# spot_check.net
KiCad netlist of a schematic drawn in EAGLE
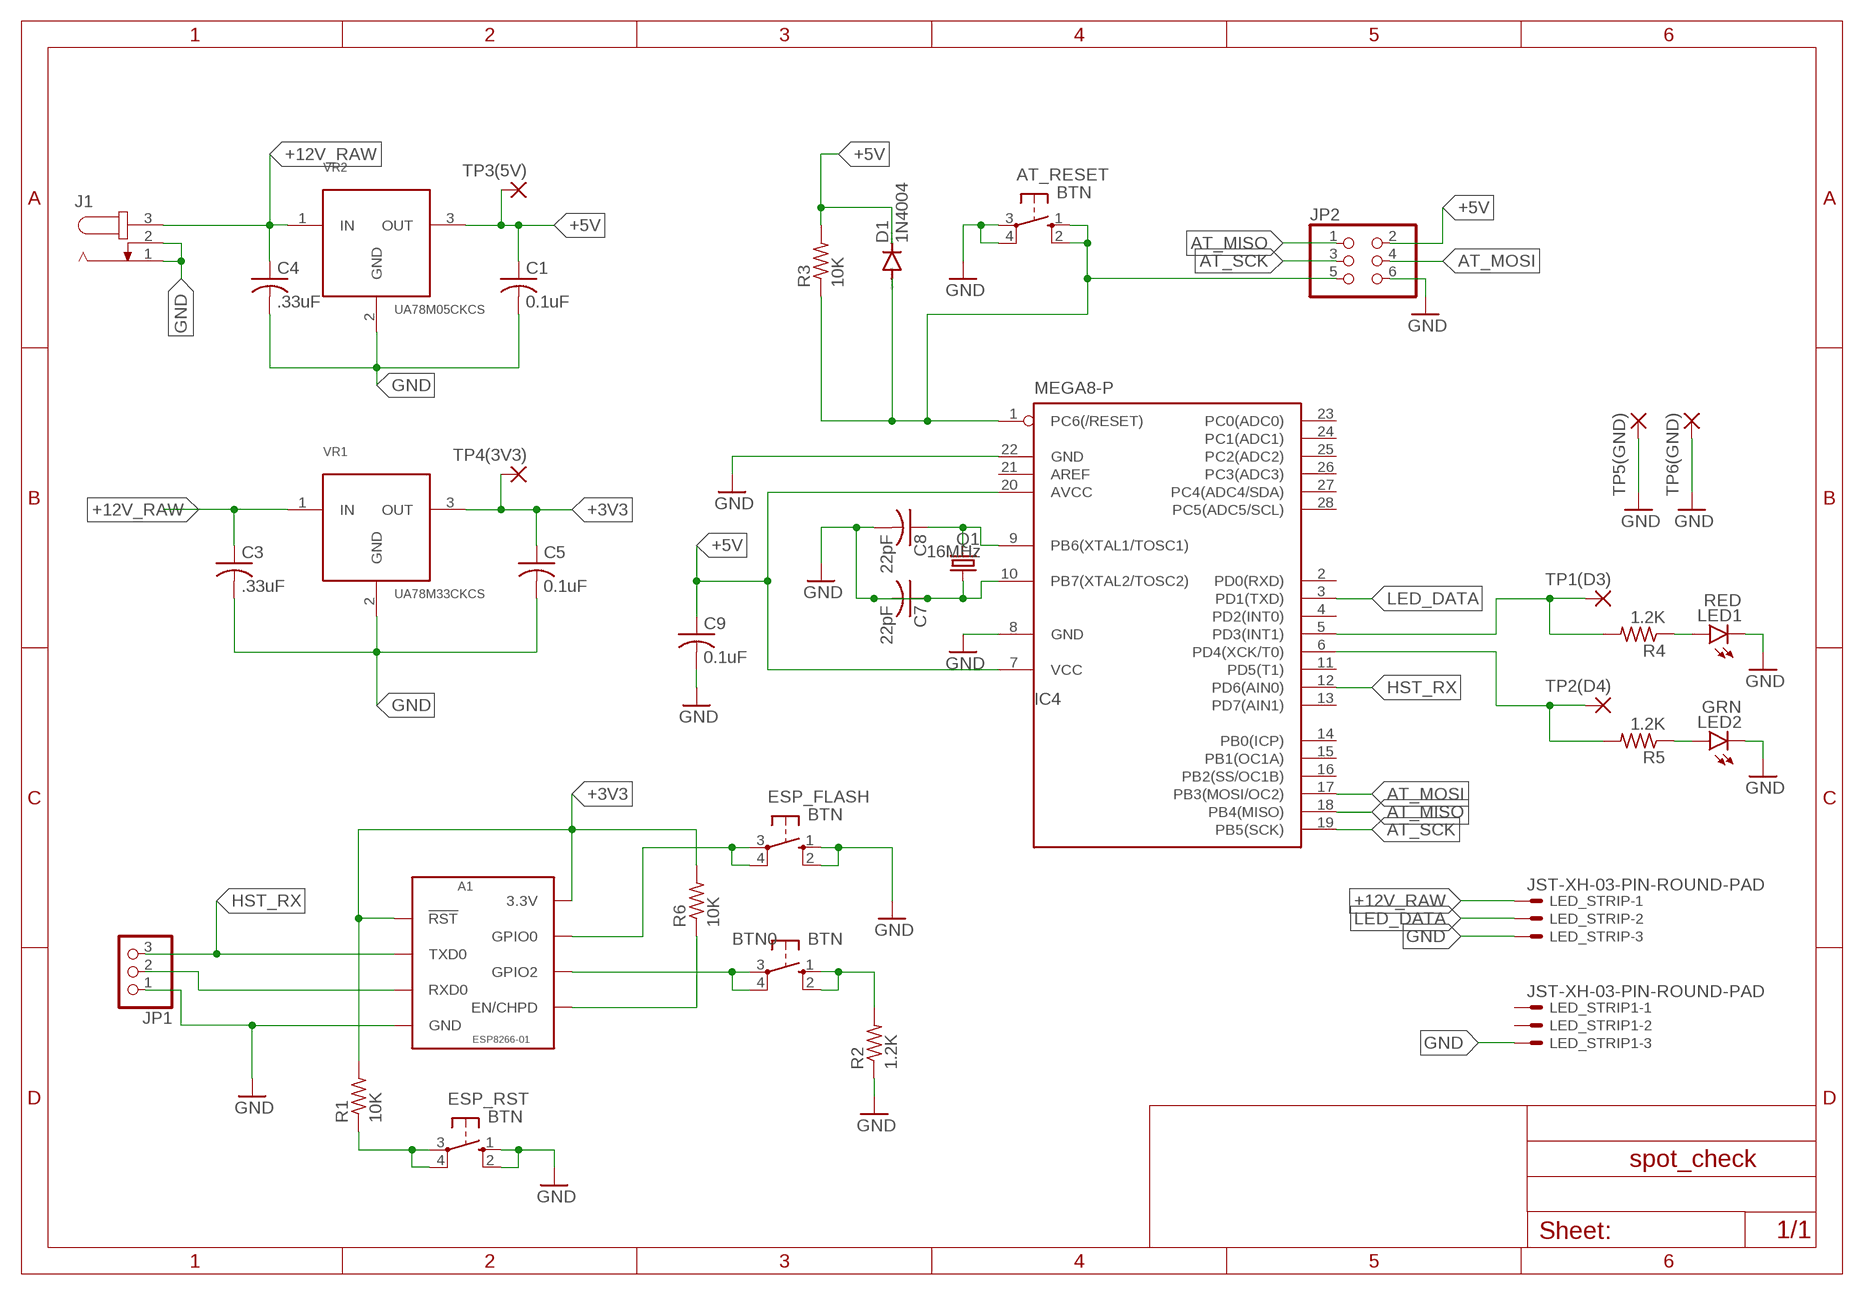
[diagram p0: schematic, sheet 1]

(export (version "E")
  (design (tool "Eeschema 10.0.6"))
  (components
    (comp (ref "A1")
      (value "ESP8266-01")
      (footprint "eagle-import:ESP8266_ESP-01_NO-SILKSCREEN")
      (fields (field (name "SPICEPREFIX") "X"))
      (libsource (lib "eagle-import") (part "ESP8266_ESP-?01"))
    )
    (comp (ref "AT_RESET")
      (value "BTN")
      (footprint "eagle-import:B3F-10XX")
      (fields (field (name "MPN") "B3F-1000") (field (name "SPICEPREFIX") "E"))
      (libsource (lib "eagle-import") (part "10-XX"))
    )
    (comp (ref "BTN0")
      (value "BTN")
      (footprint "eagle-import:B3F-10XX")
      (fields (field (name "MPN") "B3F-1000") (field (name "SPICEPREFIX") "E"))
      (libsource (lib "eagle-import") (part "10-XX"))
    )
    (comp (ref "C1")
      (value "0.1uF")
      (footprint "eagle-import:C050-024X044")
      (libsource (lib "eagle-import") (part "C-US050-024X044"))
    )
    (comp (ref "C3")
      (value ".33uF")
      (footprint "eagle-import:C050-024X044")
      (libsource (lib "eagle-import") (part "C-US050-024X044"))
    )
    (comp (ref "C4")
      (value ".33uF")
      (footprint "eagle-import:C050-024X044")
      (libsource (lib "eagle-import") (part "C-US050-024X044"))
    )
    (comp (ref "C5")
      (value "0.1uF")
      (footprint "eagle-import:C050-024X044")
      (libsource (lib "eagle-import") (part "C-US050-024X044"))
    )
    (comp (ref "C7")
      (value "22pF")
      (footprint "eagle-import:C050-024X044")
      (libsource (lib "eagle-import") (part "C-US050-024X044"))
    )
    (comp (ref "C8")
      (value "22pF")
      (footprint "eagle-import:C050-024X044")
      (libsource (lib "eagle-import") (part "C-US050-024X044"))
    )
    (comp (ref "C9")
      (value "0.1uF")
      (footprint "eagle-import:C050-024X044")
      (libsource (lib "eagle-import") (part "C-US050-024X044"))
    )
    (comp (ref "D1")
      (value "1N4004")
      (footprint "eagle-import:DO41-10")
      (fields (field (name "SPICEPREFIX") "D"))
      (libsource (lib "eagle-import") (part "1N4004"))
    )
    (comp (ref "ESP_FLASH")
      (value "BTN")
      (footprint "eagle-import:B3F-10XX")
      (fields (field (name "MPN") "B3F-1000") (field (name "SPICEPREFIX") "E"))
      (libsource (lib "eagle-import") (part "10-XX"))
    )
    (comp (ref "ESP_RST")
      (value "BTN")
      (footprint "eagle-import:B3F-10XX")
      (fields (field (name "MPN") "B3F-1000") (field (name "SPICEPREFIX") "E"))
      (libsource (lib "eagle-import") (part "10-XX"))
    )
    (comp (ref "IC4")
      (value "MEGA8-P")
      (footprint "eagle-import:DIL28-3")
      (fields (field (name "SPICEPREFIX") "X"))
      (libsource (lib "eagle-import") (part "MEGA8-P"))
    )
    (comp (ref "J1")
      (value "JACK-PLUG1")
      (footprint "eagle-import:SPC4078")
      (fields (field (name "SPICEPREFIX") "J"))
      (libsource (lib "eagle-import") (part "JACK-PLUG1"))
    )
    (comp (ref "JP1")
      (value "PINHD-1X3/90")
      (footprint "eagle-import:1X03_90")
      (fields (field (name "SPICEPREFIX") "J"))
      (libsource (lib "eagle-import") (part "PINHD-1X3/90"))
    )
    (comp (ref "JP2")
      (value "PINHD-2X3")
      (footprint "eagle-import:2X03")
      (fields (field (name "SPICEPREFIX") "X"))
      (libsource (lib "eagle-import") (part "PINHD-2X3"))
    )
    (comp (ref "LED1")
      (value "RED")
      (footprint "eagle-import:LED5MM")
      (fields (field (name "SPICEPREFIX") "L"))
      (libsource (lib "eagle-import") (part "LED5MM"))
    )
    (comp (ref "LED2")
      (value "GRN")
      (footprint "eagle-import:LED5MM")
      (fields (field (name "SPICEPREFIX") "L"))
      (libsource (lib "eagle-import") (part "LED5MM"))
    )
    (comp (ref "LED_STRIP")
      (value "JST-XH-03-PIN-ROUND-PAD")
      (footprint "eagle-import:JST-XH-03-PACKAGE-ROUND-PAD")
      (fields (field (name "SPICEPREFIX") "X"))
      (libsource (lib "eagle-import") (part "JST-XH-03-PIN-ROUND-PAD"))
    )
    (comp (ref "LED_STRIP1")
      (value "JST-XH-03-PIN-ROUND-PAD")
      (footprint "eagle-import:JST-XH-03-PACKAGE-ROUND-PAD")
      (fields (field (name "SPICEPREFIX") "X"))
      (libsource (lib "eagle-import") (part "JST-XH-03-PIN-ROUND-PAD"))
    )
    (comp (ref "Q1")
      (value "16MHz")
      (footprint "eagle-import:HC49_S")
      (fields (field (name "SPICEPREFIX") "B"))
      (libsource (lib "eagle-import") (part "CRYSTALHC49S"))
    )
    (comp (ref "R1")
      (value "10K")
      (footprint "eagle-import:0207_10")
      (libsource (lib "eagle-import") (part "R-US_0207/10"))
    )
    (comp (ref "R2")
      (value "1.2K")
      (footprint "eagle-import:0207_10")
      (libsource (lib "eagle-import") (part "R-US_0207/10"))
    )
    (comp (ref "R3")
      (value "10K")
      (footprint "eagle-import:0207_10")
      (libsource (lib "eagle-import") (part "R-US_0207/10"))
    )
    (comp (ref "R4")
      (value "1.2K")
      (footprint "eagle-import:0207_10")
      (libsource (lib "eagle-import") (part "R-US_0207/10"))
    )
    (comp (ref "R5")
      (value "1.2K")
      (footprint "eagle-import:0207_10")
      (libsource (lib "eagle-import") (part "R-US_0207/10"))
    )
    (comp (ref "R6")
      (value "10K")
      (footprint "eagle-import:0207_10")
      (libsource (lib "eagle-import") (part "R-US_0207/10"))
    )
    (comp (ref "TP1(D3)")
      (value "2,54/0,8")
      (footprint "eagle-import:2,54_0,8")
      (fields (field (name "SPICEPREFIX") "X"))
      (libsource (lib "eagle-import") (part "2,54/0,8"))
    )
    (comp (ref "TP2(D4)")
      (value "2,54/0,8")
      (footprint "eagle-import:2,54_0,8")
      (fields (field (name "SPICEPREFIX") "X"))
      (libsource (lib "eagle-import") (part "2,54/0,8"))
    )
    (comp (ref "TP3(5V)")
      (value "2,54/0,8")
      (footprint "eagle-import:2,54_0,8")
      (fields (field (name "SPICEPREFIX") "X"))
      (libsource (lib "eagle-import") (part "2,54/0,8"))
    )
    (comp (ref "TP4(3V3)")
      (value "2,54/0,8")
      (footprint "eagle-import:2,54_0,8")
      (fields (field (name "SPICEPREFIX") "X"))
      (libsource (lib "eagle-import") (part "2,54/0,8"))
    )
    (comp (ref "TP5(GND)")
      (value "2,54/0,8")
      (footprint "eagle-import:2,54_0,8")
      (fields (field (name "SPICEPREFIX") "X"))
      (libsource (lib "eagle-import") (part "2,54/0,8"))
    )
    (comp (ref "TP6(GND)")
      (value "2,54/0,8")
      (footprint "eagle-import:2,54_0,8")
      (fields (field (name "SPICEPREFIX") "X"))
      (libsource (lib "eagle-import") (part "2,54/0,8"))
    )
    (comp (ref "VR1")
      (value "UA78M33CKCS")
      (footprint "eagle-import:TO-220-3")
      (fields (field (name "SPICEPREFIX") "J"))
      (libsource (lib "eagle-import") (part "UA78M33CKCS"))
    )
    (comp (ref "VR2")
      (value "UA78M05CKCS")
      (footprint "eagle-import:TO-220-3")
      (fields (field (name "SPICEPREFIX") "J"))
      (libsource (lib "eagle-import") (part "UA78M33CKCS"))
    )
  )
  (nets
    (net (code "1") (name "+3V3") (class "Default")
      (node (ref "A1") (pin "3V3") (pinfunction "3.3V_3V3") (pintype "passive"))
      (node (ref "A1") (pin "RST") (pinfunction "~{RST}_RST") (pintype "bidirectional"))
      (node (ref "C5") (pin "1") (pinfunction "1_1") (pintype "passive"))
      (node (ref "R1") (pin "2") (pinfunction "2_2") (pintype "passive"))
      (node (ref "R6") (pin "2") (pinfunction "2_2") (pintype "passive"))
      (node (ref "TP4(3V3)") (pin "1") (pinfunction "P_1") (pintype "passive"))
      (node (ref "VR1") (pin "3") (pinfunction "OUT_3") (pintype "output"))
    )
    (net (code "2") (name "+5V") (class "Default")
      (node (ref "C1") (pin "1") (pinfunction "1_1") (pintype "passive"))
      (node (ref "C9") (pin "1") (pinfunction "1_1") (pintype "passive"))
      (node (ref "D1") (pin "C") (pinfunction "C_C") (pintype "passive"))
      (node (ref "IC4") (pin "20") (pinfunction "AVCC_20") (pintype "power_in"))
      (node (ref "IC4") (pin "7") (pinfunction "VCC_7") (pintype "power_in"))
      (node (ref "JP2") (pin "2") (pinfunction "2_2") (pintype "passive"))
      (node (ref "R3") (pin "2") (pinfunction "2_2") (pintype "passive"))
      (node (ref "TP3(5V)") (pin "1") (pinfunction "P_1") (pintype "passive"))
      (node (ref "VR2") (pin "3") (pinfunction "OUT_3") (pintype "output"))
    )
    (net (code "3") (name "+12V_RAW") (class "Default")
      (node (ref "C3") (pin "1") (pinfunction "1_1") (pintype "passive"))
      (node (ref "C4") (pin "1") (pinfunction "1_1") (pintype "passive"))
      (node (ref "J1") (pin "3") (pinfunction "3_3") (pintype "passive"))
      (node (ref "LED_STRIP") (pin "1") (pinfunction "S_1") (pintype "passive"))
      (node (ref "VR1") (pin "1") (pinfunction "IN_1") (pintype "input"))
      (node (ref "VR2") (pin "1") (pinfunction "IN_1") (pintype "input"))
    )
    (net (code "4") (name "AT_MISO") (class "Default")
      (node (ref "IC4") (pin "18") (pinfunction "PB4(MISO)_18") (pintype "bidirectional"))
      (node (ref "JP2") (pin "1") (pinfunction "1_1") (pintype "passive"))
    )
    (net (code "5") (name "AT_MOSI") (class "Default")
      (node (ref "IC4") (pin "17") (pinfunction "PB3(MOSI/OC2)_17") (pintype "bidirectional"))
      (node (ref "JP2") (pin "4") (pinfunction "4_4") (pintype "passive"))
    )
    (net (code "6") (name "AT_SCK") (class "Default")
      (node (ref "IC4") (pin "19") (pinfunction "PB5(SCK)_19") (pintype "bidirectional"))
      (node (ref "JP2") (pin "3") (pinfunction "3_3") (pintype "passive"))
    )
    (net (code "7") (name "GND") (class "Default")
      (node (ref "A1") (pin "GND") (pinfunction "GND_GND") (pintype "passive"))
      (node (ref "AT_RESET") (pin "3") (pinfunction "P_3") (pintype "passive"))
      (node (ref "AT_RESET") (pin "4") (pinfunction "P1_4") (pintype "passive"))
      (node (ref "C1") (pin "2") (pinfunction "2_2") (pintype "passive"))
      (node (ref "C3") (pin "2") (pinfunction "2_2") (pintype "passive"))
      (node (ref "C4") (pin "2") (pinfunction "2_2") (pintype "passive"))
      (node (ref "C5") (pin "2") (pinfunction "2_2") (pintype "passive"))
      (node (ref "C7") (pin "1") (pinfunction "1_1") (pintype "passive"))
      (node (ref "C7") (pin "2") (pinfunction "2_2") (pintype "passive"))
      (node (ref "C8") (pin "2") (pinfunction "2_2") (pintype "passive"))
      (node (ref "C9") (pin "2") (pinfunction "2_2") (pintype "passive"))
      (node (ref "ESP_FLASH") (pin "1") (pinfunction "S_1") (pintype "passive"))
      (node (ref "ESP_FLASH") (pin "2") (pinfunction "S1_2") (pintype "passive"))
      (node (ref "ESP_RST") (pin "1") (pinfunction "S_1") (pintype "passive"))
      (node (ref "ESP_RST") (pin "2") (pinfunction "S1_2") (pintype "passive"))
      (node (ref "IC4") (pin "10") (pinfunction "PB7(XTAL2/TOSC2)_10") (pintype "bidirectional"))
      (node (ref "IC4") (pin "22") (pinfunction "GND_22") (pintype "power_in"))
      (node (ref "IC4") (pin "8") (pinfunction "GND_8") (pintype "power_in"))
      (node (ref "J1") (pin "1") (pinfunction "1_1") (pintype "passive"))
      (node (ref "J1") (pin "2") (pinfunction "2_2") (pintype "passive"))
      (node (ref "JP1") (pin "1") (pinfunction "1_1") (pintype "passive"))
      (node (ref "JP2") (pin "6") (pinfunction "6_6") (pintype "passive"))
      (node (ref "LED1") (pin "K") (pinfunction "C_K") (pintype "passive"))
      (node (ref "LED2") (pin "K") (pinfunction "C_K") (pintype "passive"))
      (node (ref "LED_STRIP") (pin "3") (pinfunction "S_3") (pintype "passive"))
      (node (ref "LED_STRIP1") (pin "3") (pinfunction "S_3") (pintype "passive"))
      (node (ref "Q1") (pin "1") (pinfunction "1_1") (pintype "passive"))
      (node (ref "R2") (pin "1") (pinfunction "1_1") (pintype "passive"))
      (node (ref "TP5(GND)") (pin "1") (pinfunction "P_1") (pintype "passive"))
      (node (ref "TP6(GND)") (pin "1") (pinfunction "P_1") (pintype "passive"))
      (node (ref "VR1") (pin "2") (pinfunction "GND_2") (pintype "bidirectional"))
      (node (ref "VR2") (pin "2") (pinfunction "GND_2") (pintype "bidirectional"))
    )
    (net (code "8") (name "HST_RX") (class "Default")
      (node (ref "A1") (pin "TX") (pinfunction "TXD0_TX") (pintype "bidirectional"))
      (node (ref "IC4") (pin "12") (pinfunction "PD6(AIN0)_12") (pintype "bidirectional"))
      (node (ref "JP1") (pin "3") (pinfunction "3_3") (pintype "passive"))
    )
    (net (code "9") (name "LED_DATA") (class "Default")
      (node (ref "IC4") (pin "3") (pinfunction "PD1(TXD)_3") (pintype "bidirectional"))
      (node (ref "LED_STRIP") (pin "2") (pinfunction "S_2") (pintype "passive"))
    )
    (net (code "10") (name "Net-(A1-EN{slash}CHPD)") (class "Default")
      (node (ref "A1") (pin "EN/CH_PD") (pinfunction "EN/CHPD_EN/CH_PD") (pintype "bidirectional"))
      (node (ref "R6") (pin "1") (pinfunction "1_1") (pintype "passive"))
    )
    (net (code "11") (name "Net-(A1-RXD0)") (class "Default")
      (node (ref "A1") (pin "RX") (pinfunction "RXD0_RX") (pintype "bidirectional"))
      (node (ref "JP1") (pin "2") (pinfunction "2_2") (pintype "passive"))
    )
    (net (code "12") (name "Net-(AT_RESET-S)") (class "Default")
      (node (ref "AT_RESET") (pin "1") (pinfunction "S_1") (pintype "passive"))
      (node (ref "AT_RESET") (pin "2") (pinfunction "S1_2") (pintype "passive"))
      (node (ref "D1") (pin "A") (pinfunction "A_A") (pintype "passive"))
      (node (ref "IC4") (pin "1") (pinfunction "PC6(/RESET)_1") (pintype "bidirectional"))
      (node (ref "JP2") (pin "5") (pinfunction "5_5") (pintype "passive"))
      (node (ref "R3") (pin "1") (pinfunction "1_1") (pintype "passive"))
    )
    (net (code "13") (name "Net-(BTN0-P)") (class "Default")
      (node (ref "A1") (pin "GPIO2") (pinfunction "GPIO2_GPIO2") (pintype "bidirectional"))
      (node (ref "BTN0") (pin "3") (pinfunction "P_3") (pintype "passive"))
      (node (ref "BTN0") (pin "4") (pinfunction "P1_4") (pintype "passive"))
    )
    (net (code "14") (name "Net-(BTN0-S)") (class "Default")
      (node (ref "BTN0") (pin "1") (pinfunction "S_1") (pintype "passive"))
      (node (ref "BTN0") (pin "2") (pinfunction "S1_2") (pintype "passive"))
      (node (ref "R2") (pin "2") (pinfunction "2_2") (pintype "passive"))
    )
    (net (code "15") (name "Net-(ESP_FLASH-P)") (class "Default")
      (node (ref "A1") (pin "GPIO0") (pinfunction "GPIO0_GPIO0") (pintype "bidirectional"))
      (node (ref "ESP_FLASH") (pin "3") (pinfunction "P_3") (pintype "passive"))
      (node (ref "ESP_FLASH") (pin "4") (pinfunction "P1_4") (pintype "passive"))
    )
    (net (code "16") (name "Net-(ESP_RST-P)") (class "Default")
      (node (ref "ESP_RST") (pin "3") (pinfunction "P_3") (pintype "passive"))
      (node (ref "ESP_RST") (pin "4") (pinfunction "P1_4") (pintype "passive"))
      (node (ref "R1") (pin "1") (pinfunction "1_1") (pintype "passive"))
    )
    (net (code "17") (name "Net-(IC4-PB6(XTAL1{slash}TOSC1))") (class "Default")
      (node (ref "C8") (pin "1") (pinfunction "1_1") (pintype "passive"))
      (node (ref "IC4") (pin "9") (pinfunction "PB6(XTAL1/TOSC1)_9") (pintype "bidirectional"))
      (node (ref "Q1") (pin "2") (pinfunction "2_2") (pintype "passive"))
    )
    (net (code "18") (name "Net-(IC4-PD3(INT1))") (class "Default")
      (node (ref "IC4") (pin "5") (pinfunction "PD3(INT1)_5") (pintype "bidirectional"))
      (node (ref "R4") (pin "2") (pinfunction "2_2") (pintype "passive"))
      (node (ref "TP1(D3)") (pin "1") (pinfunction "P_1") (pintype "passive"))
    )
    (net (code "19") (name "Net-(IC4-PD4(XCK{slash}T0))") (class "Default")
      (node (ref "IC4") (pin "6") (pinfunction "PD4(XCK/T0)_6") (pintype "bidirectional"))
      (node (ref "R5") (pin "2") (pinfunction "2_2") (pintype "passive"))
      (node (ref "TP2(D4)") (pin "1") (pinfunction "P_1") (pintype "passive"))
    )
    (net (code "20") (name "Net-(LED1-PadA)") (class "Default")
      (node (ref "LED1") (pin "A") (pinfunction "A_A") (pintype "passive"))
      (node (ref "R4") (pin "1") (pinfunction "1_1") (pintype "passive"))
    )
    (net (code "21") (name "Net-(LED2-PadA)") (class "Default")
      (node (ref "LED2") (pin "A") (pinfunction "A_A") (pintype "passive"))
      (node (ref "R5") (pin "1") (pinfunction "1_1") (pintype "passive"))
    )
    (net (code "22") (name "unconnected-(IC4-AREF-Pad21)") (class "Default")
      (node (ref "IC4") (pin "21") (pinfunction "AREF_21") (pintype "passive"))
    )
    (net (code "23") (name "unconnected-(IC4-PB0(ICP)-Pad14)") (class "Default")
      (node (ref "IC4") (pin "14") (pinfunction "PB0(ICP)_14") (pintype "bidirectional"))
    )
    (net (code "24") (name "unconnected-(IC4-PB1(OC1A)-Pad15)") (class "Default")
      (node (ref "IC4") (pin "15") (pinfunction "PB1(OC1A)_15") (pintype "bidirectional"))
    )
    (net (code "25") (name "unconnected-(IC4-PB2(SS{slash}OC1B)-Pad16)") (class "Default")
      (node (ref "IC4") (pin "16") (pinfunction "PB2(SS/OC1B)_16") (pintype "bidirectional"))
    )
    (net (code "26") (name "unconnected-(IC4-PC0(ADC0)-Pad23)") (class "Default")
      (node (ref "IC4") (pin "23") (pinfunction "PC0(ADC0)_23") (pintype "bidirectional"))
    )
    (net (code "27") (name "unconnected-(IC4-PC1(ADC1)-Pad24)") (class "Default")
      (node (ref "IC4") (pin "24") (pinfunction "PC1(ADC1)_24") (pintype "bidirectional"))
    )
    (net (code "28") (name "unconnected-(IC4-PC2(ADC2)-Pad25)") (class "Default")
      (node (ref "IC4") (pin "25") (pinfunction "PC2(ADC2)_25") (pintype "bidirectional"))
    )
    (net (code "29") (name "unconnected-(IC4-PC3(ADC3)-Pad26)") (class "Default")
      (node (ref "IC4") (pin "26") (pinfunction "PC3(ADC3)_26") (pintype "bidirectional"))
    )
    (net (code "30") (name "unconnected-(IC4-PC4(ADC4{slash}SDA)-Pad27)") (class "Default")
      (node (ref "IC4") (pin "27") (pinfunction "PC4(ADC4/SDA)_27") (pintype "bidirectional"))
    )
    (net (code "31") (name "unconnected-(IC4-PC5(ADC5{slash}SCL)-Pad28)") (class "Default")
      (node (ref "IC4") (pin "28") (pinfunction "PC5(ADC5/SCL)_28") (pintype "bidirectional"))
    )
    (net (code "32") (name "unconnected-(IC4-PD0(RXD)-Pad2)") (class "Default")
      (node (ref "IC4") (pin "2") (pinfunction "PD0(RXD)_2") (pintype "bidirectional"))
    )
    (net (code "33") (name "unconnected-(IC4-PD2(INT0)-Pad4)") (class "Default")
      (node (ref "IC4") (pin "4") (pinfunction "PD2(INT0)_4") (pintype "bidirectional"))
    )
    (net (code "34") (name "unconnected-(IC4-PD5(T1)-Pad11)") (class "Default")
      (node (ref "IC4") (pin "11") (pinfunction "PD5(T1)_11") (pintype "bidirectional"))
    )
    (net (code "35") (name "unconnected-(IC4-PD7(AIN1)-Pad13)") (class "Default")
      (node (ref "IC4") (pin "13") (pinfunction "PD7(AIN1)_13") (pintype "bidirectional"))
    )
    (net (code "36") (name "unconnected-(LED_STRIP1A-S-Pad1)") (class "Default")
      (node (ref "LED_STRIP1") (pin "1") (pinfunction "S_1") (pintype "passive"))
    )
    (net (code "37") (name "unconnected-(LED_STRIP1B-S-Pad2)") (class "Default")
      (node (ref "LED_STRIP1") (pin "2") (pinfunction "S_2") (pintype "passive"))
    )
  )
)
